# KorszeInterfaces.net
KiCad netlist of a schematic drawn in Altium Designer
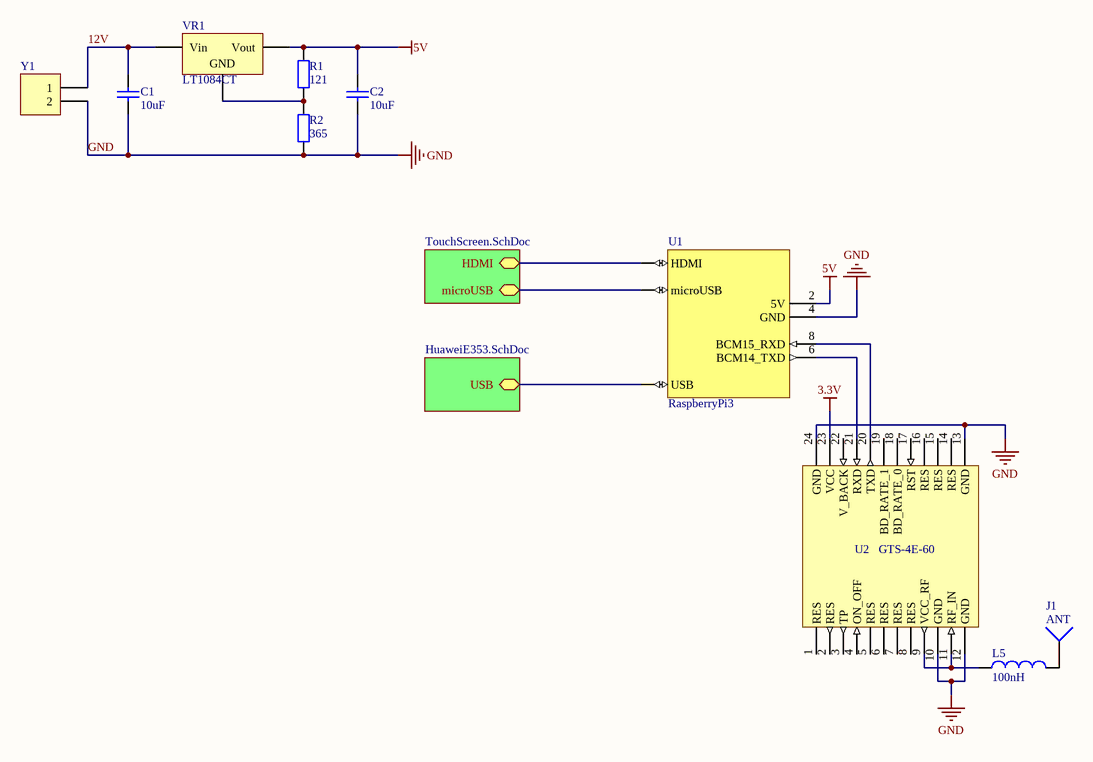
[diagram p0: KorszeInterfaces.SchDoc]

(export (version "E")
  (design (tool "Eeschema 10.0.6"))
  (components
    (comp (ref "C1")
      (value "10uF")
      (footprint "RAD-0.3")
      (description "Capacitor")
      (fields (field (name "PUBLISHER") "Altium Limited"))
      (libsource (lib "Miscellaneous Devices") (part "Cap"))
    )
    (comp (ref "C2")
      (value "10uF")
      (footprint "RAD-0.3")
      (description "Capacitor")
      (fields (field (name "PUBLISHER") "Altium Limited"))
      (libsource (lib "Miscellaneous Devices") (part "Cap"))
    )
    (comp (ref "J1")
      (value "ANT")
      (footprint "PIN1")
      (description "Socket")
      (fields (field (name "PUBLISHER") "Altium Limited"))
      (libsource (lib "Miscellaneous Connectors") (part "Socket"))
    )
    (comp (ref "L5")
      (value "100nH")
      (footprint "0402-A")
      (description "Inductor")
      (fields (field (name "PUBLISHER") "Altium Limited"))
      (libsource (lib "Miscellaneous Devices") (part "Inductor"))
    )
    (comp (ref "R1")
      (value "121")
      (footprint "AXIAL-0.4")
      (description "Resistor")
      (fields (field (name "PUBLISHER") "Altium Limited"))
      (libsource (lib "Miscellaneous Devices") (part "Res2"))
    )
    (comp (ref "R2")
      (value "365")
      (footprint "AXIAL-0.4")
      (description "Resistor")
      (fields (field (name "PUBLISHER") "Altium Limited"))
      (libsource (lib "Miscellaneous Devices") (part "Res2"))
    )
    (comp (ref "U1") (value "RaspberryPi3") (libsource (lib "Raspberry") (part "RaspberryPi3")))
    (comp (ref "U2")
      (value "GTS-4E-60")
      (description "FIBOCOM GTS-4E-60, GPS Module")
      (libsource (lib "FIBOCOM") (part "GTS-4E-60"))
    )
    (comp (ref "VR1")
      (value "LT1084CT")
      (footprint "TO-220-AB")
      (description "Voltage Regulator")
      (fields (field (name "PUBLISHER") "Altium Limited"))
      (libsource (lib "Miscellaneous Devices") (part "Volt Reg"))
    )
    (comp (ref "Y1")
      (value "Header 2H")
      (footprint "HDR1X2H")
      (description "Header, 2-Pin, Right Angle")
      (fields (field (name "PUBLISHER") "Altium Limited"))
      (libsource (lib "Miscellaneous Connectors") (part "Header 2H"))
    )
  )
  (nets
    (net (code "1") (name "/12V") (class "Default")
      (node (ref "C1") (pin "2") (pinfunction "2_2") (pintype "passive"))
      (node (ref "VR1") (pin "1") (pinfunction "Vin_1") (pintype "passive"))
      (node (ref "Y1") (pin "1") (pinfunction "1_1") (pintype "passive"))
    )
    (net (code "2") (name "/HDMI") (class "Default")
      (node (ref "U1") (pin "") (pinfunction "HDMI_") (pintype "bidirectional"))
    )
    (net (code "3") (name "/USB") (class "Default")
      (node (ref "U1") (pin "") (pinfunction "USB_") (pintype "bidirectional"))
    )
    (net (code "4") (name "/microUSB") (class "Default")
      (node (ref "U1") (pin "") (pinfunction "microUSB_") (pintype "bidirectional"))
    )
    (net (code "5") (name "3.3V") (class "Default")
      (node (ref "U2") (pin "23") (pinfunction "VCC_23") (pintype "power_in"))
    )
    (net (code "6") (name "5V") (class "Default")
      (node (ref "C2") (pin "2") (pinfunction "2_2") (pintype "passive"))
      (node (ref "R1") (pin "2") (pinfunction "2_2") (pintype "passive"))
      (node (ref "U1") (pin "2") (pinfunction "5V_2") (pintype "power_in"))
      (node (ref "VR1") (pin "3") (pinfunction "Vout_3") (pintype "passive"))
    )
    (net (code "7") (name "GND") (class "Default")
      (node (ref "C1") (pin "1") (pinfunction "1_1") (pintype "passive"))
      (node (ref "C2") (pin "1") (pinfunction "1_1") (pintype "passive"))
      (node (ref "R2") (pin "1") (pinfunction "1_1") (pintype "passive"))
      (node (ref "U1") (pin "4") (pinfunction "GND_4") (pintype "power_in"))
      (node (ref "U2") (pin "10") (pinfunction "GND_10") (pintype "power_in"))
      (node (ref "U2") (pin "12") (pinfunction "GND_12") (pintype "power_in"))
      (node (ref "U2") (pin "13") (pinfunction "GND_13") (pintype "power_in"))
      (node (ref "U2") (pin "24") (pinfunction "GND_24") (pintype "power_in"))
      (node (ref "Y1") (pin "2") (pinfunction "2_2") (pintype "passive"))
    )
    (net (code "8") (name "Net-(J1-Pad1)") (class "Default")
      (node (ref "J1") (pin "1") (pinfunction "1_1") (pintype "passive"))
      (node (ref "L5") (pin "2") (pinfunction "2_2") (pintype "passive"))
    )
    (net (code "9") (name "Net-(U1-BCM14_TXD)") (class "Default")
      (node (ref "U1") (pin "6") (pinfunction "BCM14_TXD_6") (pintype "output"))
      (node (ref "U2") (pin "21") (pinfunction "RXD_21") (pintype "input"))
    )
    (net (code "10") (name "Net-(U1-BCM15_RXD)") (class "Default")
      (node (ref "U1") (pin "8") (pinfunction "BCM15_RXD_8") (pintype "input"))
      (node (ref "U2") (pin "20") (pinfunction "TXD_20") (pintype "output"))
    )
    (net (code "11") (name "Net-(U2-RF_IN)") (class "Default")
      (node (ref "L5") (pin "1") (pinfunction "1_1") (pintype "passive"))
      (node (ref "U2") (pin "11") (pinfunction "RF_IN_11") (pintype "input"))
      (node (ref "U2") (pin "9") (pinfunction "VCC_RF_9") (pintype "output"))
    )
    (net (code "12") (name "Net-(VR1-GND)") (class "Default")
      (node (ref "R1") (pin "1") (pinfunction "1_1") (pintype "passive"))
      (node (ref "R2") (pin "2") (pinfunction "2_2") (pintype "passive"))
      (node (ref "VR1") (pin "2") (pinfunction "GND_2") (pintype "passive"))
    )
    (net (code "13") (name "unconnected-(U2-BD_RATE_0-Pad18)") (class "Default")
      (node (ref "U2") (pin "18") (pinfunction "BD_RATE_0_18") (pintype "passive"))
    )
    (net (code "14") (name "unconnected-(U2-BD_RATE_1-Pad19)") (class "Default")
      (node (ref "U2") (pin "19") (pinfunction "BD_RATE_1_19") (pintype "passive"))
    )
    (net (code "15") (name "unconnected-(U2-ON_OFF-Pad4)") (class "Default")
      (node (ref "U2") (pin "4") (pinfunction "ON_OFF_4") (pintype "input"))
    )
    (net (code "16") (name "unconnected-(U2-RES-Pad1)") (class "Default")
      (node (ref "U2") (pin "1") (pinfunction "RES_1") (pintype "passive"))
    )
    (net (code "17") (name "unconnected-(U2-RES-Pad2)") (class "Default")
      (node (ref "U2") (pin "2") (pinfunction "RES_2") (pintype "output"))
    )
    (net (code "18") (name "unconnected-(U2-RES-Pad5)") (class "Default")
      (node (ref "U2") (pin "5") (pinfunction "RES_5") (pintype "passive"))
    )
    (net (code "19") (name "unconnected-(U2-RES-Pad6)") (class "Default")
      (node (ref "U2") (pin "6") (pinfunction "RES_6") (pintype "passive"))
    )
    (net (code "20") (name "unconnected-(U2-RES-Pad7)") (class "Default")
      (node (ref "U2") (pin "7") (pinfunction "RES_7") (pintype "passive"))
    )
    (net (code "21") (name "unconnected-(U2-RES-Pad8)") (class "Default")
      (node (ref "U2") (pin "8") (pinfunction "RES_8") (pintype "passive"))
    )
    (net (code "22") (name "unconnected-(U2-RES-Pad14)") (class "Default")
      (node (ref "U2") (pin "14") (pinfunction "RES_14") (pintype "passive"))
    )
    (net (code "23") (name "unconnected-(U2-RES-Pad15)") (class "Default")
      (node (ref "U2") (pin "15") (pinfunction "RES_15") (pintype "passive"))
    )
    (net (code "24") (name "unconnected-(U2-RES-Pad16)") (class "Default")
      (node (ref "U2") (pin "16") (pinfunction "RES_16") (pintype "passive"))
    )
    (net (code "25") (name "unconnected-(U2-RST-Pad17)") (class "Default")
      (node (ref "U2") (pin "17") (pinfunction "RST_17") (pintype "input"))
    )
    (net (code "26") (name "unconnected-(U2-TP-Pad3)") (class "Default")
      (node (ref "U2") (pin "3") (pinfunction "TP_3") (pintype "output"))
    )
    (net (code "27") (name "unconnected-(U2-V_BACK-Pad22)") (class "Default")
      (node (ref "U2") (pin "22") (pinfunction "V_BACK_22") (pintype "input"))
    )
  )
)
